# Nodemcu_Zeno_Version_2021-05-12.net
KiCad netlist of a schematic drawn in EasyEDA
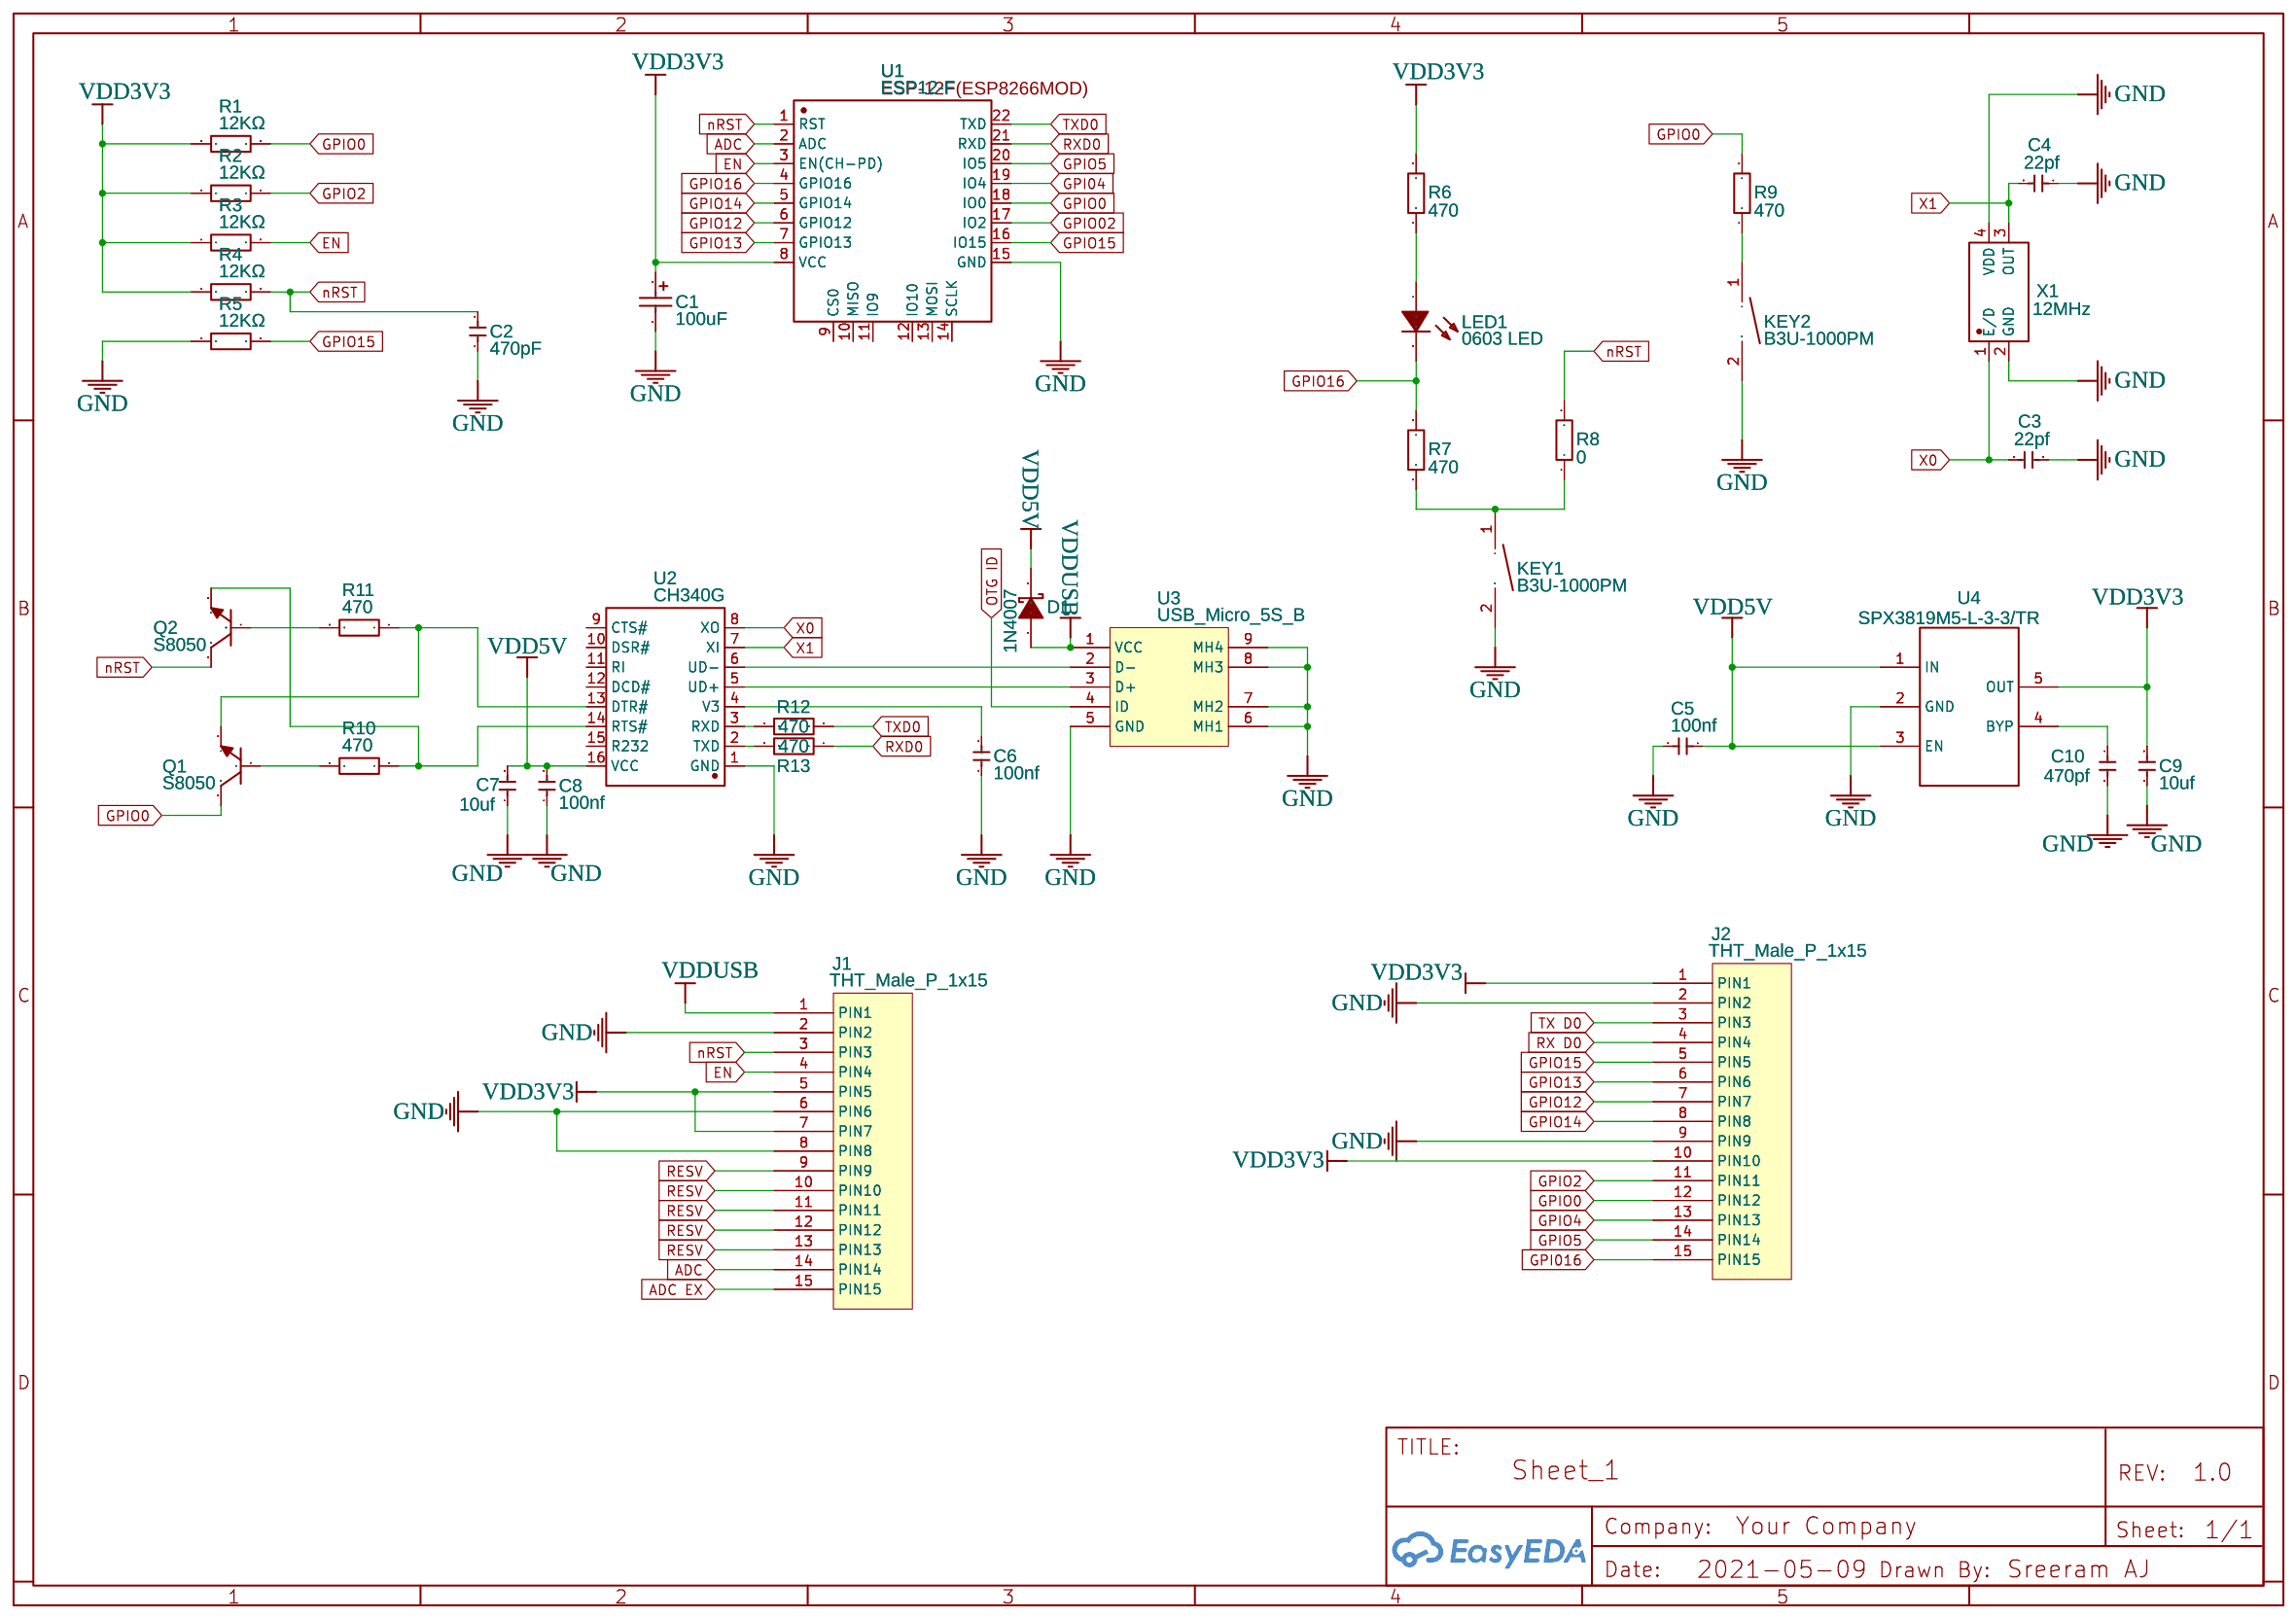
[diagram p0: schematic sheet]

(export (version "E")
  (design (tool "Eeschema 10.0.6"))
  (components
    (comp (ref "C1")
      (value "100uF")
      (fields
        (field (name "BOM_Manufacturer Part") "TAJB107M006RNJ")
        (field (name "BOM_Supplier Part") "C7195")
      )
      (libsource (lib "") (part "TAJB107M006RNJ"))
    )
    (comp (ref "C2") (value "470pF") (libsource (lib "") (part "470pF")))
    (comp (ref "C3") (value "22pf") (libsource (lib "") (part "470pF_1")))
    (comp (ref "C4") (value "22pf") (libsource (lib "") (part "470pF_1")))
    (comp (ref "C5") (value "100nf") (libsource (lib "") (part "470pF_1")))
    (comp (ref "C6") (value "100nf") (libsource (lib "") (part "470pF")))
    (comp (ref "C7") (value "10uf") (libsource (lib "") (part "470pF")))
    (comp (ref "C8") (value "100nf") (libsource (lib "") (part "470pF")))
    (comp (ref "C9") (value "10uf") (libsource (lib "") (part "470pF")))
    (comp (ref "C10") (value "470pf") (libsource (lib "") (part "470pF_2")))
    (comp (ref "D1")
      (value "1N4007")
      (fields (field (name "BOM_Manufacturer Part") "SS310") (field (name "BOM_Supplier Part") "C85658"))
      (libsource (lib "") (part "SS310_C85658"))
    )
    (comp (ref "J1") (value "THT_Male_P_1x15") (libsource (lib "") (part "THT_Male_P_1x15")))
    (comp (ref "J2") (value "THT_Male_P_1x15") (libsource (lib "") (part "THT_Male_P_1x15")))
    (comp (ref "KEY1")
      (value "B3U-1000PM")
      (fields (field (name "BOM_Supplier Part") "C271754"))
      (libsource (lib "") (part "B3U-1000PM"))
    )
    (comp (ref "KEY2")
      (value "B3U-1000PM")
      (fields (field (name "BOM_Supplier Part") "C271754"))
      (libsource (lib "") (part "B3U-1000PM"))
    )
    (comp (ref "LED1")
      (value "0603 LED")
      (fields
        (field (name "BOM_Manufacturer Part") "E6C0603UYAC1UDA")
        (field (name "BOM_Supplier Part") "C375445")
      )
      (libsource (lib "") (part "0603 LED"))
    )
    (comp (ref "Q1")
      (value "S8050")
      (fields (field (name "BOM_Supplier Part") "C916390"))
      (libsource (lib "") (part "S8050"))
    )
    (comp (ref "Q2")
      (value "S8050")
      (fields (field (name "BOM_Supplier Part") "C916390"))
      (libsource (lib "") (part "S8050"))
    )
    (comp (ref "R1")
      (value "12KΩ")
      (fields
        (field (name "BOM_Manufacturer Part") "0603WAF1202T5E")
        (field (name "BOM_Supplier Part") "C22790")
      )
      (libsource (lib "") (part "12K Resistor SMD 0603 (C22790)"))
    )
    (comp (ref "R2")
      (value "12KΩ")
      (fields
        (field (name "BOM_Manufacturer Part") "0603WAF1202T5E")
        (field (name "BOM_Supplier Part") "C22790")
      )
      (libsource (lib "") (part "12K Resistor SMD 0603 (C22790)"))
    )
    (comp (ref "R3")
      (value "12KΩ")
      (fields
        (field (name "BOM_Manufacturer Part") "0603WAF1202T5E")
        (field (name "BOM_Supplier Part") "C22790")
      )
      (libsource (lib "") (part "12K Resistor SMD 0603 (C22790)"))
    )
    (comp (ref "R4")
      (value "12KΩ")
      (fields
        (field (name "BOM_Manufacturer Part") "0603WAF1202T5E")
        (field (name "BOM_Supplier Part") "C22790")
      )
      (libsource (lib "") (part "12K Resistor SMD 0603 (C22790)"))
    )
    (comp (ref "R5")
      (value "12KΩ")
      (fields
        (field (name "BOM_Manufacturer Part") "0603WAF1202T5E")
        (field (name "BOM_Supplier Part") "C22790")
      )
      (libsource (lib "") (part "12K Resistor SMD 0603 (C22790)"))
    )
    (comp (ref "R6")
      (value "470")
      (fields
        (field (name "BOM_Manufacturer Part") "0603WAF1202T5E")
        (field (name "BOM_Supplier Part") "C22790")
      )
      (libsource (lib "") (part "12K Resistor SMD 0603 (C22790)_2"))
    )
    (comp (ref "R7")
      (value "470")
      (fields
        (field (name "BOM_Manufacturer Part") "0603WAF1202T5E")
        (field (name "BOM_Supplier Part") "C22790")
      )
      (libsource (lib "") (part "12K Resistor SMD 0603 (C22790)_2"))
    )
    (comp (ref "R8")
      (value "0")
      (fields
        (field (name "BOM_Manufacturer Part") "0603WAF1202T5E")
        (field (name "BOM_Supplier Part") "C22790")
      )
      (libsource (lib "") (part "12K Resistor SMD 0603 (C22790)_2"))
    )
    (comp (ref "R9")
      (value "470")
      (fields
        (field (name "BOM_Manufacturer Part") "0603WAF1202T5E")
        (field (name "BOM_Supplier Part") "C22790")
      )
      (libsource (lib "") (part "12K Resistor SMD 0603 (C22790)_2"))
    )
    (comp (ref "R10")
      (value "470")
      (fields
        (field (name "BOM_Manufacturer Part") "0603WAF1202T5E")
        (field (name "BOM_Supplier Part") "C22790")
      )
      (libsource (lib "") (part "12K Resistor SMD 0603 (C22790)_1"))
    )
    (comp (ref "R11")
      (value "470")
      (fields
        (field (name "BOM_Manufacturer Part") "0603WAF1202T5E")
        (field (name "BOM_Supplier Part") "C22790")
      )
      (libsource (lib "") (part "12K Resistor SMD 0603 (C22790)_1"))
    )
    (comp (ref "R12")
      (value "470")
      (fields
        (field (name "BOM_Manufacturer Part") "0603WAF1202T5E")
        (field (name "BOM_Supplier Part") "C22790")
      )
      (libsource (lib "") (part "12K Resistor SMD 0603 (C22790)"))
    )
    (comp (ref "R13")
      (value "470")
      (fields
        (field (name "BOM_Manufacturer Part") "0603WAF1202T5E")
        (field (name "BOM_Supplier Part") "C22790")
      )
      (libsource (lib "") (part "12K Resistor SMD 0603 (C22790)_1"))
    )
    (comp (ref "U1") (value "ESP12-F") (libsource (lib "") (part "ESP12-F")))
    (comp (ref "U2")
      (value "CH340G")
      (fields (field (name "BOM_Supplier Part") "C14267"))
      (libsource (lib "") (part "CH340G"))
    )
    (comp (ref "U3") (value "USB_Micro_5S_B") (libsource (lib "") (part "USB_Micro_5S_B")))
    (comp (ref "U4")
      (value "SPX3819M5-L-3-3/TR")
      (fields (field (name "BOM_Supplier Part") "C9055"))
      (libsource (lib "") (part "SPX3819M5-L-3-3/TR"))
    )
    (comp (ref "X1")
      (value "12MHz")
      (fields
        (field (name "BOM_Manufacturer Part") "O705012MGDA4SC")
        (field (name "BOM_Supplier Part") "C70633")
      )
      (libsource (lib "") (part "O705012MGDA4SC"))
    )
  )
  (nets
    (net (code "1") (name "ADC") (class "Default")
      (node (ref "J1") (pin "14") (pinfunction "PIN14_14") (pintype "unspecified"))
      (node (ref "U1") (pin "2") (pinfunction "ADC_2") (pintype "unspecified"))
    )
    (net (code "2") (name "ADC EX") (class "Default")
      (node (ref "J1") (pin "15") (pinfunction "PIN15_15") (pintype "unspecified"))
    )
    (net (code "3") (name "EN") (class "Default")
      (node (ref "J1") (pin "4") (pinfunction "PIN4_4") (pintype "unspecified"))
      (node (ref "R3") (pin "2") (pinfunction "2_2") (pintype "input"))
      (node (ref "U1") (pin "3") (pinfunction "EN(CH-PD)_3") (pintype "unspecified"))
    )
    (net (code "4") (name "GND") (class "Default")
      (node (ref "C1") (pin "2") (pinfunction "2_2") (pintype "input"))
      (node (ref "C10") (pin "2") (pinfunction "2_2") (pintype "unspecified"))
      (node (ref "C2") (pin "1") (pinfunction "1_1") (pintype "unspecified"))
      (node (ref "C3") (pin "1") (pinfunction "1_1") (pintype "unspecified"))
      (node (ref "C4") (pin "1") (pinfunction "1_1") (pintype "unspecified"))
      (node (ref "C5") (pin "2") (pinfunction "2_2") (pintype "unspecified"))
      (node (ref "C6") (pin "1") (pinfunction "1_1") (pintype "unspecified"))
      (node (ref "C7") (pin "1") (pinfunction "1_1") (pintype "unspecified"))
      (node (ref "C8") (pin "1") (pinfunction "1_1") (pintype "unspecified"))
      (node (ref "C9") (pin "1") (pinfunction "1_1") (pintype "unspecified"))
      (node (ref "J1") (pin "2") (pinfunction "PIN2_2") (pintype "unspecified"))
      (node (ref "J1") (pin "6") (pinfunction "PIN6_6") (pintype "unspecified"))
      (node (ref "J1") (pin "8") (pinfunction "PIN8_8") (pintype "unspecified"))
      (node (ref "J2") (pin "2") (pinfunction "PIN2_2") (pintype "unspecified"))
      (node (ref "J2") (pin "9") (pinfunction "PIN9_9") (pintype "unspecified"))
      (node (ref "KEY1") (pin "2") (pinfunction "2_2") (pintype "input"))
      (node (ref "KEY2") (pin "2") (pinfunction "2_2") (pintype "input"))
      (node (ref "R5") (pin "1") (pinfunction "1_1") (pintype "input"))
      (node (ref "U1") (pin "15") (pinfunction "GND_15") (pintype "unspecified"))
      (node (ref "U2") (pin "1") (pinfunction "GND_1") (pintype "unspecified"))
      (node (ref "U3") (pin "5") (pinfunction "GND_5") (pintype "unspecified"))
      (node (ref "U3") (pin "6") (pinfunction "MH1_6") (pintype "unspecified"))
      (node (ref "U3") (pin "7") (pinfunction "MH2_7") (pintype "unspecified"))
      (node (ref "U3") (pin "8") (pinfunction "MH3_8") (pintype "unspecified"))
      (node (ref "U3") (pin "9") (pinfunction "MH4_9") (pintype "unspecified"))
      (node (ref "U4") (pin "2") (pinfunction "GND_2") (pintype "unspecified"))
      (node (ref "X1") (pin "2") (pinfunction "GND_2") (pintype "unspecified"))
      (node (ref "X1") (pin "4") (pinfunction "VDD_4") (pintype "unspecified"))
    )
    (net (code "5") (name "GPI04") (class "Default")
      (node (ref "U1") (pin "19") (pinfunction "IO4_19") (pintype "unspecified"))
    )
    (net (code "6") (name "GPI016") (class "Default")
      (node (ref "J2") (pin "15") (pinfunction "PIN15_15") (pintype "unspecified"))
    )
    (net (code "7") (name "GPIO0") (class "Default")
      (node (ref "J2") (pin "12") (pinfunction "PIN12_12") (pintype "unspecified"))
      (node (ref "Q1") (pin "3") (pinfunction "C_3") (pintype "input"))
      (node (ref "R1") (pin "2") (pinfunction "2_2") (pintype "input"))
      (node (ref "R9") (pin "2") (pinfunction "2_2") (pintype "input"))
      (node (ref "U1") (pin "18") (pinfunction "IO0_18") (pintype "unspecified"))
    )
    (net (code "8") (name "GPIO2") (class "Default")
      (node (ref "J2") (pin "11") (pinfunction "PIN11_11") (pintype "unspecified"))
      (node (ref "R2") (pin "2") (pinfunction "2_2") (pintype "input"))
    )
    (net (code "9") (name "GPIO02") (class "Default")
      (node (ref "U1") (pin "17") (pinfunction "IO2_17") (pintype "unspecified"))
    )
    (net (code "10") (name "GPIO4") (class "Default")
      (node (ref "J2") (pin "13") (pinfunction "PIN13_13") (pintype "unspecified"))
    )
    (net (code "11") (name "GPIO5") (class "Default")
      (node (ref "J2") (pin "14") (pinfunction "PIN14_14") (pintype "unspecified"))
      (node (ref "U1") (pin "20") (pinfunction "IO5_20") (pintype "unspecified"))
    )
    (net (code "12") (name "GPIO12") (class "Default")
      (node (ref "J2") (pin "7") (pinfunction "PIN7_7") (pintype "unspecified"))
      (node (ref "U1") (pin "6") (pinfunction "GPIO12_6") (pintype "unspecified"))
    )
    (net (code "13") (name "GPIO13") (class "Default")
      (node (ref "J2") (pin "6") (pinfunction "PIN6_6") (pintype "unspecified"))
      (node (ref "U1") (pin "7") (pinfunction "GPIO13_7") (pintype "unspecified"))
    )
    (net (code "14") (name "GPIO14") (class "Default")
      (node (ref "J2") (pin "8") (pinfunction "PIN8_8") (pintype "unspecified"))
      (node (ref "U1") (pin "5") (pinfunction "GPIO14_5") (pintype "unspecified"))
    )
    (net (code "15") (name "GPIO15") (class "Default")
      (node (ref "J2") (pin "5") (pinfunction "PIN5_5") (pintype "unspecified"))
      (node (ref "R5") (pin "2") (pinfunction "2_2") (pintype "input"))
      (node (ref "U1") (pin "16") (pinfunction "IO15_16") (pintype "unspecified"))
    )
    (net (code "16") (name "GPIO16") (class "Default")
      (node (ref "LED1") (pin "2") (pinfunction "-_2") (pintype "unspecified"))
      (node (ref "R7") (pin "2") (pinfunction "2_2") (pintype "input"))
      (node (ref "U1") (pin "4") (pinfunction "GPIO16_4") (pintype "unspecified"))
    )
    (net (code "17") (name "Net-(KEY1-Pad1)") (class "Default")
      (node (ref "KEY1") (pin "1") (pinfunction "1_1") (pintype "input"))
      (node (ref "R7") (pin "1") (pinfunction "1_1") (pintype "input"))
      (node (ref "R8") (pin "1") (pinfunction "1_1") (pintype "input"))
    )
    (net (code "18") (name "Net-(KEY2-Pad1)") (class "Default")
      (node (ref "KEY2") (pin "1") (pinfunction "1_1") (pintype "input"))
      (node (ref "R9") (pin "1") (pinfunction "1_1") (pintype "input"))
    )
    (net (code "19") (name "Net-(LED1-+)") (class "Default")
      (node (ref "LED1") (pin "1") (pinfunction "+_1") (pintype "unspecified"))
      (node (ref "R6") (pin "1") (pinfunction "1_1") (pintype "input"))
    )
    (net (code "20") (name "Net-(Q1-B)") (class "Default")
      (node (ref "Q1") (pin "1") (pinfunction "B_1") (pintype "input"))
      (node (ref "R10") (pin "2") (pinfunction "2_2") (pintype "input"))
    )
    (net (code "21") (name "Net-(Q1-E)") (class "Default")
      (node (ref "Q1") (pin "2") (pinfunction "E_2") (pintype "input"))
      (node (ref "R11") (pin "1") (pinfunction "1_1") (pintype "input"))
      (node (ref "U2") (pin "13") (pinfunction "DTR#_13") (pintype "unspecified"))
    )
    (net (code "22") (name "Net-(Q2-B)") (class "Default")
      (node (ref "Q2") (pin "1") (pinfunction "B_1") (pintype "input"))
      (node (ref "R11") (pin "2") (pinfunction "2_2") (pintype "input"))
    )
    (net (code "23") (name "Net-(Q2-E)") (class "Default")
      (node (ref "Q2") (pin "2") (pinfunction "E_2") (pintype "input"))
      (node (ref "R10") (pin "1") (pinfunction "1_1") (pintype "input"))
      (node (ref "U2") (pin "14") (pinfunction "RTS#_14") (pintype "unspecified"))
    )
    (net (code "24") (name "Net-(U2-RXD)") (class "Default")
      (node (ref "R12") (pin "1") (pinfunction "1_1") (pintype "input"))
      (node (ref "U2") (pin "3") (pinfunction "RXD_3") (pintype "unspecified"))
    )
    (net (code "25") (name "Net-(U2-TXD)") (class "Default")
      (node (ref "R13") (pin "2") (pinfunction "2_2") (pintype "input"))
      (node (ref "U2") (pin "2") (pinfunction "TXD_2") (pintype "unspecified"))
    )
    (net (code "26") (name "Net-(U2-UD+)") (class "Default")
      (node (ref "U2") (pin "5") (pinfunction "UD+_5") (pintype "unspecified"))
      (node (ref "U3") (pin "3") (pinfunction "D+_3") (pintype "unspecified"))
    )
    (net (code "27") (name "Net-(U2-UD-)") (class "Default")
      (node (ref "U2") (pin "6") (pinfunction "UD-_6") (pintype "unspecified"))
      (node (ref "U3") (pin "2") (pinfunction "D-_2") (pintype "unspecified"))
    )
    (net (code "28") (name "Net-(U2-V3)") (class "Default")
      (node (ref "C6") (pin "2") (pinfunction "2_2") (pintype "unspecified"))
      (node (ref "U2") (pin "4") (pinfunction "V3_4") (pintype "unspecified"))
    )
    (net (code "29") (name "Net-(U4-BYP)") (class "Default")
      (node (ref "C10") (pin "1") (pinfunction "1_1") (pintype "unspecified"))
      (node (ref "U4") (pin "4") (pinfunction "BYP_4") (pintype "unspecified"))
    )
    (net (code "30") (name "OTG ID") (class "Default")
      (node (ref "U3") (pin "4") (pinfunction "ID_4") (pintype "unspecified"))
    )
    (net (code "31") (name "RESV") (class "Default")
      (node (ref "J1") (pin "10") (pinfunction "PIN10_10") (pintype "unspecified"))
      (node (ref "J1") (pin "11") (pinfunction "PIN11_11") (pintype "unspecified"))
      (node (ref "J1") (pin "12") (pinfunction "PIN12_12") (pintype "unspecified"))
      (node (ref "J1") (pin "13") (pinfunction "PIN13_13") (pintype "unspecified"))
      (node (ref "J1") (pin "9") (pinfunction "PIN9_9") (pintype "unspecified"))
    )
    (net (code "32") (name "RX D0") (class "Default")
      (node (ref "J2") (pin "4") (pinfunction "PIN4_4") (pintype "unspecified"))
    )
    (net (code "33") (name "RXD0") (class "Default")
      (node (ref "R13") (pin "1") (pinfunction "1_1") (pintype "input"))
      (node (ref "U1") (pin "21") (pinfunction "RXD_21") (pintype "unspecified"))
    )
    (net (code "34") (name "TX D0") (class "Default")
      (node (ref "J2") (pin "3") (pinfunction "PIN3_3") (pintype "unspecified"))
    )
    (net (code "35") (name "TXD0") (class "Default")
      (node (ref "R12") (pin "2") (pinfunction "2_2") (pintype "input"))
      (node (ref "U1") (pin "22") (pinfunction "TXD_22") (pintype "unspecified"))
    )
    (net (code "36") (name "VDD3V3") (class "Default")
      (node (ref "C1") (pin "1") (pinfunction "1_1") (pintype "input"))
      (node (ref "C9") (pin "2") (pinfunction "2_2") (pintype "unspecified"))
      (node (ref "J1") (pin "5") (pinfunction "PIN5_5") (pintype "unspecified"))
      (node (ref "J1") (pin "7") (pinfunction "PIN7_7") (pintype "unspecified"))
      (node (ref "J2") (pin "1") (pinfunction "PIN1_1") (pintype "unspecified"))
      (node (ref "J2") (pin "10") (pinfunction "PIN10_10") (pintype "unspecified"))
      (node (ref "R1") (pin "1") (pinfunction "1_1") (pintype "input"))
      (node (ref "R2") (pin "1") (pinfunction "1_1") (pintype "input"))
      (node (ref "R3") (pin "1") (pinfunction "1_1") (pintype "input"))
      (node (ref "R4") (pin "1") (pinfunction "1_1") (pintype "input"))
      (node (ref "R6") (pin "2") (pinfunction "2_2") (pintype "input"))
      (node (ref "U1") (pin "8") (pinfunction "VCC_8") (pintype "unspecified"))
      (node (ref "U4") (pin "5") (pinfunction "OUT_5") (pintype "unspecified"))
    )
    (net (code "37") (name "VDD5V") (class "Default")
      (node (ref "C5") (pin "1") (pinfunction "1_1") (pintype "unspecified"))
      (node (ref "C7") (pin "2") (pinfunction "2_2") (pintype "unspecified"))
      (node (ref "C8") (pin "2") (pinfunction "2_2") (pintype "unspecified"))
      (node (ref "D1") (pin "1") (pinfunction "K_1") (pintype "unspecified"))
      (node (ref "U2") (pin "16") (pinfunction "VCC_16") (pintype "unspecified"))
      (node (ref "U4") (pin "1") (pinfunction "IN_1") (pintype "unspecified"))
      (node (ref "U4") (pin "3") (pinfunction "EN_3") (pintype "unspecified"))
    )
    (net (code "38") (name "VDDUSB") (class "Default")
      (node (ref "D1") (pin "2") (pinfunction "A_2") (pintype "unspecified"))
      (node (ref "J1") (pin "1") (pinfunction "PIN1_1") (pintype "unspecified"))
      (node (ref "U3") (pin "1") (pinfunction "VCC_1") (pintype "unspecified"))
    )
    (net (code "39") (name "X0") (class "Default")
      (node (ref "C3") (pin "2") (pinfunction "2_2") (pintype "unspecified"))
      (node (ref "U2") (pin "8") (pinfunction "XO_8") (pintype "unspecified"))
      (node (ref "X1") (pin "1") (pinfunction "E/D_1") (pintype "unspecified"))
    )
    (net (code "40") (name "X1") (class "Default")
      (node (ref "C4") (pin "2") (pinfunction "2_2") (pintype "unspecified"))
      (node (ref "U2") (pin "7") (pinfunction "XI_7") (pintype "unspecified"))
      (node (ref "X1") (pin "3") (pinfunction "OUT_3") (pintype "unspecified"))
    )
    (net (code "41") (name "nRST") (class "Default")
      (node (ref "C2") (pin "2") (pinfunction "2_2") (pintype "unspecified"))
      (node (ref "J1") (pin "3") (pinfunction "PIN3_3") (pintype "unspecified"))
      (node (ref "Q2") (pin "3") (pinfunction "C_3") (pintype "input"))
      (node (ref "R4") (pin "2") (pinfunction "2_2") (pintype "input"))
      (node (ref "R8") (pin "2") (pinfunction "2_2") (pintype "input"))
      (node (ref "U1") (pin "1") (pinfunction "RST_1") (pintype "unspecified"))
    )
    (net (code "42") (name "unconnected-(U1-CS0-Pad9)") (class "Default")
      (node (ref "U1") (pin "9") (pinfunction "CS0_9") (pintype "unspecified"))
    )
    (net (code "43") (name "unconnected-(U1-IO9-Pad11)") (class "Default")
      (node (ref "U1") (pin "11") (pinfunction "IO9_11") (pintype "unspecified"))
    )
    (net (code "44") (name "unconnected-(U1-IO10-Pad12)") (class "Default")
      (node (ref "U1") (pin "12") (pinfunction "IO10_12") (pintype "unspecified"))
    )
    (net (code "45") (name "unconnected-(U1-MISO-Pad10)") (class "Default")
      (node (ref "U1") (pin "10") (pinfunction "MISO_10") (pintype "unspecified"))
    )
    (net (code "46") (name "unconnected-(U1-MOSI-Pad13)") (class "Default")
      (node (ref "U1") (pin "13") (pinfunction "MOSI_13") (pintype "unspecified"))
    )
    (net (code "47") (name "unconnected-(U1-SCLK-Pad14)") (class "Default")
      (node (ref "U1") (pin "14") (pinfunction "SCLK_14") (pintype "unspecified"))
    )
    (net (code "48") (name "unconnected-(U2-CTS#-Pad9)") (class "Default")
      (node (ref "U2") (pin "9") (pinfunction "CTS#_9") (pintype "unspecified"))
    )
    (net (code "49") (name "unconnected-(U2-DCD#-Pad12)") (class "Default")
      (node (ref "U2") (pin "12") (pinfunction "DCD#_12") (pintype "unspecified"))
    )
    (net (code "50") (name "unconnected-(U2-DSR#-Pad10)") (class "Default")
      (node (ref "U2") (pin "10") (pinfunction "DSR#_10") (pintype "unspecified"))
    )
    (net (code "51") (name "unconnected-(U2-R232-Pad15)") (class "Default")
      (node (ref "U2") (pin "15") (pinfunction "R232_15") (pintype "unspecified"))
    )
    (net (code "52") (name "unconnected-(U2-RI-Pad11)") (class "Default")
      (node (ref "U2") (pin "11") (pinfunction "RI_11") (pintype "unspecified"))
    )
  )
)
